# ZLS_Signal_Conditioner.net
KiCad netlist of a schematic drawn in Altium Designer
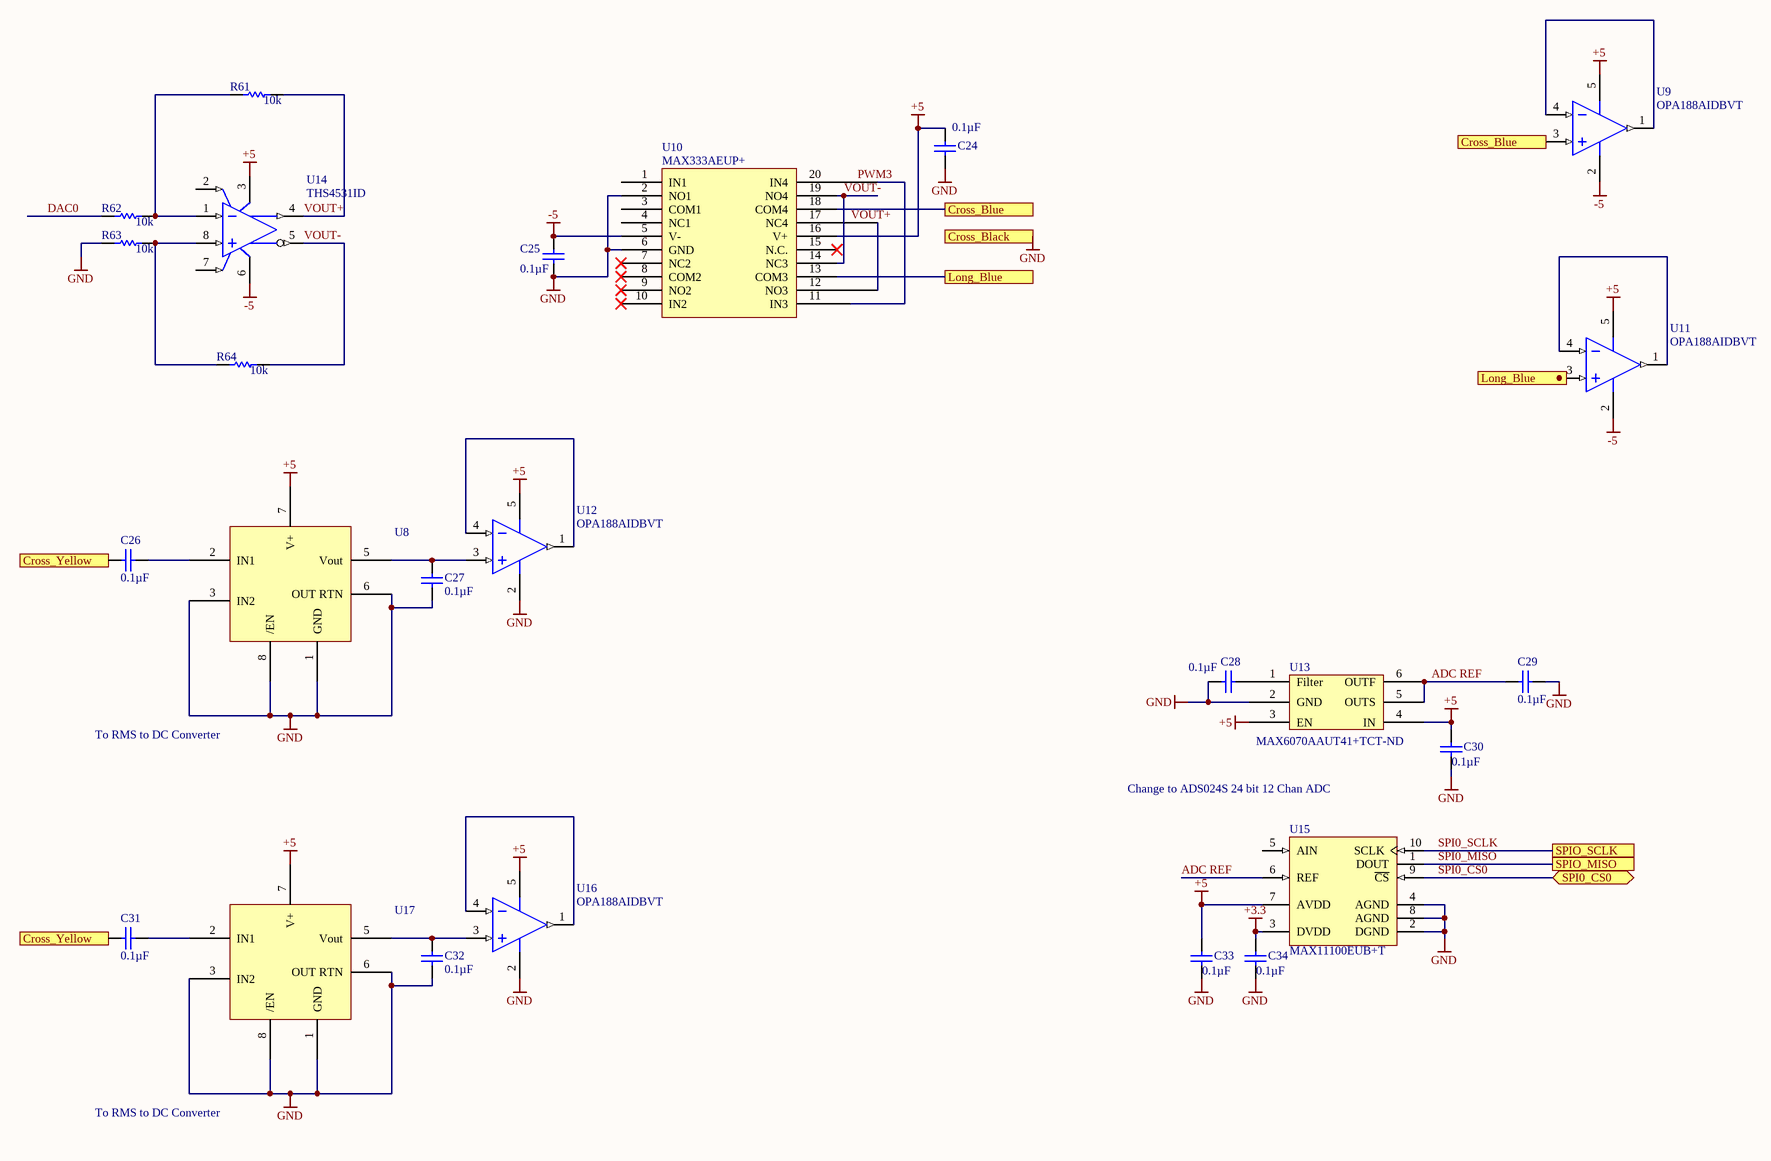
[diagram p0: ZLS_Signal_Conditioner.SchDoc]

(export (version "E")
  (design (tool "Eeschema 10.0.6"))
  (components
    (comp (ref "C24")
      (value "CAP CER 0.1UF 25V X7R 0805")
      (footprint "CAPC0805(2012)145_N")
      (fields
        (field (name "MANUFACTURER") "Murata Electronics North America")
        (field (name "MANUFACTURER PART NUMBER") "GRM21BR71E104KA01L")
        (field (name "CAPACITANCE") "0.1µF")
        (field (name "TOLERANCE") "±10%")
      )
      (libsource (lib "Altium Content Vault") (part "CMP-1036-04795-1"))
    )
    (comp (ref "C25")
      (value "CAP CER 0.1UF 25V X7R 0805")
      (footprint "CAPC0805(2012)145_N")
      (fields
        (field (name "MANUFACTURER") "Murata Electronics North America")
        (field (name "MANUFACTURER PART NUMBER") "GRM21BR71E104KA01L")
        (field (name "CAPACITANCE") "0.1µF")
        (field (name "TOLERANCE") "±10%")
      )
      (libsource (lib "Altium Content Vault") (part "CMP-1036-04795-1"))
    )
    (comp (ref "C26")
      (value "CAP CER 0.1UF 25V X7R 0805")
      (footprint "CAPC0805(2012)145_N")
      (fields
        (field (name "MANUFACTURER") "Murata Electronics North America")
        (field (name "MANUFACTURER PART NUMBER") "GRM21BR71E104KA01L")
        (field (name "CAPACITANCE") "0.1µF")
        (field (name "TOLERANCE") "±10%")
      )
      (libsource (lib "Altium Content Vault") (part "CMP-1036-04795-1"))
    )
    (comp (ref "C27")
      (value "CAP CER 0.1UF 25V X7R 0805")
      (footprint "CAPC0805(2012)145_N")
      (fields
        (field (name "MANUFACTURER") "Murata Electronics North America")
        (field (name "MANUFACTURER PART NUMBER") "GRM21BR71E104KA01L")
        (field (name "CAPACITANCE") "0.1µF")
        (field (name "TOLERANCE") "±10%")
      )
      (libsource (lib "Altium Content Vault") (part "CMP-1036-04795-1"))
    )
    (comp (ref "C28")
      (value "CAP CER 0.1UF 25V X7R 0805")
      (footprint "CAPC0805(2012)145_N")
      (fields
        (field (name "MANUFACTURER") "Murata Electronics North America")
        (field (name "MANUFACTURER PART NUMBER") "GRM21BR71E104KA01L")
        (field (name "CAPACITANCE") "0.1µF")
        (field (name "TOLERANCE") "±10%")
      )
      (libsource (lib "Altium Content Vault") (part "CMP-1036-04795-1"))
    )
    (comp (ref "C29")
      (value "CAP CER 0.1UF 25V X7R 0805")
      (footprint "CAPC0805(2012)145_N")
      (fields
        (field (name "MANUFACTURER") "Murata Electronics North America")
        (field (name "MANUFACTURER PART NUMBER") "GRM21BR71E104KA01L")
        (field (name "CAPACITANCE") "0.1µF")
        (field (name "TOLERANCE") "±10%")
      )
      (libsource (lib "Altium Content Vault") (part "CMP-1036-04795-1"))
    )
    (comp (ref "C30")
      (value "CAP CER 0.1UF 25V X7R 0805")
      (footprint "CAPC0805(2012)145_N")
      (fields
        (field (name "MANUFACTURER") "Murata Electronics North America")
        (field (name "MANUFACTURER PART NUMBER") "GRM21BR71E104KA01L")
        (field (name "CAPACITANCE") "0.1µF")
        (field (name "TOLERANCE") "±10%")
      )
      (libsource (lib "Altium Content Vault") (part "CMP-1036-04795-1"))
    )
    (comp (ref "C31")
      (value "CAP CER 0.1UF 25V X7R 0805")
      (footprint "CAPC0805(2012)145_N")
      (fields
        (field (name "MANUFACTURER") "Murata Electronics North America")
        (field (name "MANUFACTURER PART NUMBER") "GRM21BR71E104KA01L")
        (field (name "CAPACITANCE") "0.1µF")
        (field (name "TOLERANCE") "±10%")
      )
      (libsource (lib "Altium Content Vault") (part "CMP-1036-04795-1"))
    )
    (comp (ref "C32")
      (value "CAP CER 0.1UF 25V X7R 0805")
      (footprint "CAPC0805(2012)145_N")
      (fields
        (field (name "MANUFACTURER") "Murata Electronics North America")
        (field (name "MANUFACTURER PART NUMBER") "GRM21BR71E104KA01L")
        (field (name "CAPACITANCE") "0.1µF")
        (field (name "TOLERANCE") "±10%")
      )
      (libsource (lib "Altium Content Vault") (part "CMP-1036-04795-1"))
    )
    (comp (ref "C33")
      (value "CAP CER 0.1UF 25V X7R 0805")
      (footprint "CAPC0805(2012)145_N")
      (fields
        (field (name "MANUFACTURER") "Murata Electronics North America")
        (field (name "MANUFACTURER PART NUMBER") "GRM21BR71E104KA01L")
        (field (name "CAPACITANCE") "0.1µF")
        (field (name "TOLERANCE") "±10%")
      )
      (libsource (lib "Altium Content Vault") (part "CMP-1036-04795-1"))
    )
    (comp (ref "C34")
      (value "CAP CER 0.1UF 25V X7R 0805")
      (footprint "CAPC0805(2012)145_N")
      (fields
        (field (name "MANUFACTURER") "Murata Electronics North America")
        (field (name "MANUFACTURER PART NUMBER") "GRM21BR71E104KA01L")
        (field (name "CAPACITANCE") "0.1µF")
        (field (name "TOLERANCE") "±10%")
      )
      (libsource (lib "Altium Content Vault") (part "CMP-1036-04795-1"))
    )
    (comp (ref "R61")
      (value "10k")
      (footprint "RESC0805(2012)_L")
      (description "RES SMD 10K OHM 1% 1/8W 0805")
      (fields
        (field (name "MANUFACTURER") "Vishay Dale")
        (field (name "MANUFACTURER PART NUMBER") "CRCW080510K0FKEA")
      )
      (libsource (lib "Altium Content Vault") (part "CMP-1013-00393-1"))
    )
    (comp (ref "R62")
      (value "10k")
      (footprint "RESC0805(2012)_L")
      (description "RES SMD 10K OHM 1% 1/8W 0805")
      (fields
        (field (name "MANUFACTURER") "Vishay Dale")
        (field (name "MANUFACTURER PART NUMBER") "CRCW080510K0FKEA")
      )
      (libsource (lib "Altium Content Vault") (part "CMP-1013-00393-1"))
    )
    (comp (ref "R63")
      (value "10k")
      (footprint "RESC0805(2012)_L")
      (description "RES SMD 10K OHM 1% 1/8W 0805")
      (fields
        (field (name "MANUFACTURER") "Vishay Dale")
        (field (name "MANUFACTURER PART NUMBER") "CRCW080510K0FKEA")
      )
      (libsource (lib "Altium Content Vault") (part "CMP-1013-00393-1"))
    )
    (comp (ref "R64")
      (value "10k")
      (footprint "RESC0805(2012)_L")
      (description "RES SMD 10K OHM 1% 1/8W 0805")
      (fields
        (field (name "MANUFACTURER") "Vishay Dale")
        (field (name "MANUFACTURER PART NUMBER") "CRCW080510K0FKEA")
      )
      (libsource (lib "Altium Content Vault") (part "CMP-1013-00393-1"))
    )
    (comp (ref "U8")
      (value "LTC1967")
      (footprint "LTC1967")
      (description "IC CONVERTER RMS-DC PREC 9MSOP")
      (libsource (lib "ZLS_Schematic_lib") (part "LTC1967"))
    )
    (comp (ref "U9")
      (value "OPA188AIDBVT")
      (footprint "DBV0005A_L")
      (fields (field (name "MANUFACTURER") "Texas Instruments"))
      (libsource (lib "Altium Content Vault") (part "TI-OPA188-DBV5"))
    )
    (comp (ref "U10")
      (value "MAX333AEUP+")
      (footprint "TSOP65P640X90-20N")
      (description "IC SWITCH QUAD SPDT 20TSSOP")
      (fields (field (name "MANUFACTURER") "Maxim Integrated") (field (name "BASE PART NUMBER") "MAX333"))
      (libsource (lib "ZLS_Schematic_lib") (part "MAX333CWP+"))
    )
    (comp (ref "U11")
      (value "OPA188AIDBVT")
      (footprint "DBV0005A_L")
      (fields (field (name "MANUFACTURER") "Texas Instruments"))
      (libsource (lib "Altium Content Vault") (part "TI-OPA188-DBV5"))
    )
    (comp (ref "U12")
      (value "OPA188AIDBVT")
      (footprint "DBV0005A_L")
      (fields (field (name "MANUFACTURER") "Texas Instruments"))
      (libsource (lib "Altium Content Vault") (part "TI-OPA188-DBV5"))
    )
    (comp (ref "U13")
      (value "MAX6070AAUT41+T")
      (footprint "SOT95P280X445-6N")
      (description "IC VREF SERIES 4.096V SOT23")
      (fields
        (field (name "SUPPLIER PART NUMBER 1") "MAX6070AAUT41+TCT-ND")
        (field (name "MANUFACTURER") "Maxim Integrated")
        (field (name "TOLERANCE") "±0.04%")
      )
      (libsource (lib "ZLS_Schematic_lib") (part "MAX6070AAUT41+T"))
    )
    (comp (ref "U14")
      (value "THS4531ID")
      (footprint "D0008A_N")
      (fields (field (name "MANUFACTURER") "Texas Instruments"))
      (libsource (lib "Altium Content Vault") (part "CMP-0811-00005-2"))
    )
    (comp (ref "U15")
      (value "MAX11100EUB+T")
      (footprint "U10+2_L")
      (description "16-Bit, +5V, 200ksps ADC with 10uA Shutdown, 10-Pin uMAX, -40°C to +85°C, Pb-Free, Tape and Reel")
      (libsource (lib "Altium Content Vault") (part "CON-ADC-MAX11100-IL10"))
    )
    (comp (ref "U16")
      (value "OPA188AIDBVT")
      (footprint "DBV0005A_L")
      (fields (field (name "MANUFACTURER") "Texas Instruments"))
      (libsource (lib "Altium Content Vault") (part "TI-OPA188-DBV5"))
    )
    (comp (ref "U17")
      (value "LTC1967")
      (footprint "LTC1967")
      (description "IC CONVERTER RMS-DC PREC 9MSOP")
      (libsource (lib "ZLS_Schematic_lib") (part "LTC1967"))
    )
  )
  (nets
    (net (code "1") (name "+3.3") (class "Default")
      (node (ref "C34") (pin "1") (pinfunction "1_1") (pintype "passive"))
      (node (ref "U15") (pin "3") (pinfunction "DVDD_3") (pintype "power_in"))
    )
    (net (code "2") (name "+5") (class "Default")
      (node (ref "C24") (pin "1") (pinfunction "1_1") (pintype "passive"))
      (node (ref "C30") (pin "1") (pinfunction "1_1") (pintype "passive"))
      (node (ref "C33") (pin "1") (pinfunction "1_1") (pintype "passive"))
      (node (ref "U10") (pin "16") (pinfunction "V+_16") (pintype "power_in"))
      (node (ref "U11") (pin "5") (pinfunction "V+_5") (pintype "power_in"))
      (node (ref "U12") (pin "5") (pinfunction "V+_5") (pintype "power_in"))
      (node (ref "U13") (pin "3") (pinfunction "EN_3") (pintype "passive"))
      (node (ref "U13") (pin "4") (pinfunction "IN_4") (pintype "passive"))
      (node (ref "U14") (pin "3") (pinfunction "VS+_3") (pintype "power_in"))
      (node (ref "U15") (pin "7") (pinfunction "AVDD_7") (pintype "power_in"))
      (node (ref "U16") (pin "5") (pinfunction "V+_5") (pintype "power_in"))
      (node (ref "U17") (pin "7") (pinfunction "V+_7") (pintype "passive"))
      (node (ref "U8") (pin "7") (pinfunction "V+_7") (pintype "passive"))
      (node (ref "U9") (pin "5") (pinfunction "V+_5") (pintype "power_in"))
    )
    (net (code "3") (name "-5") (class "Default")
      (node (ref "C25") (pin "1") (pinfunction "1_1") (pintype "passive"))
      (node (ref "U10") (pin "5") (pinfunction "V-_5") (pintype "power_in"))
      (node (ref "U11") (pin "2") (pinfunction "V-_2") (pintype "power_in"))
      (node (ref "U14") (pin "6") (pinfunction "VS-_6") (pintype "power_in"))
      (node (ref "U9") (pin "2") (pinfunction "V-_2") (pintype "power_in"))
    )
    (net (code "4") (name "/ADC REF") (class "Default")
      (node (ref "C29") (pin "1") (pinfunction "1_1") (pintype "passive"))
      (node (ref "U13") (pin "5") (pinfunction "OUTS_5") (pintype "passive"))
      (node (ref "U13") (pin "6") (pinfunction "OUTF_6") (pintype "passive"))
      (node (ref "U15") (pin "6") (pinfunction "REF_6") (pintype "input"))
    )
    (net (code "5") (name "/Cross_Blue") (class "Default")
      (node (ref "U10") (pin "18") (pinfunction "COM4_18") (pintype "passive"))
      (node (ref "U9") (pin "3") (pinfunction "IN+_3") (pintype "input"))
    )
    (net (code "6") (name "/Cross_Yellow") (class "Default")
      (node (ref "C26") (pin "1") (pinfunction "1_1") (pintype "passive"))
      (node (ref "C31") (pin "1") (pinfunction "1_1") (pintype "passive"))
    )
    (net (code "7") (name "/DAC0") (class "Default")
      (node (ref "R62") (pin "1") (pinfunction "1_1") (pintype "passive"))
    )
    (net (code "8") (name "/Long_Blue") (class "Default")
      (node (ref "U10") (pin "13") (pinfunction "COM3_13") (pintype "passive"))
    )
    (net (code "9") (name "/PWM3") (class "Default")
      (node (ref "U10") (pin "11") (pinfunction "IN3_11") (pintype "passive"))
      (node (ref "U10") (pin "20") (pinfunction "IN4_20") (pintype "passive"))
    )
    (net (code "10") (name "/SPI0_CS0") (class "Default")
      (node (ref "U15") (pin "9") (pinfunction "~{CS}_9") (pintype "input"))
    )
    (net (code "11") (name "/SPI0_MISO") (class "Default")
      (node (ref "U15") (pin "1") (pinfunction "DOUT_1") (pintype "tri_state"))
    )
    (net (code "12") (name "/SPI0_SCLK") (class "Default")
      (node (ref "U15") (pin "10") (pinfunction "SCLK_10") (pintype "input"))
    )
    (net (code "13") (name "/VOUT+") (class "Default")
      (node (ref "R61") (pin "2") (pinfunction "2_2") (pintype "passive"))
      (node (ref "U10") (pin "12") (pinfunction "NO3_12") (pintype "passive"))
      (node (ref "U10") (pin "17") (pinfunction "NC4_17") (pintype "passive"))
      (node (ref "U14") (pin "4") (pinfunction "VOUT+_4") (pintype "output"))
    )
    (net (code "14") (name "/VOUT-") (class "Default")
      (node (ref "R64") (pin "2") (pinfunction "2_2") (pintype "passive"))
      (node (ref "U10") (pin "14") (pinfunction "NC3_14") (pintype "passive"))
      (node (ref "U10") (pin "19") (pinfunction "NO4_19") (pintype "passive"))
      (node (ref "U14") (pin "5") (pinfunction "VOUT-_5") (pintype "output"))
    )
    (net (code "15") (name "GND") (class "Default")
      (node (ref "C24") (pin "2") (pinfunction "2_2") (pintype "passive"))
      (node (ref "C25") (pin "2") (pinfunction "2_2") (pintype "passive"))
      (node (ref "C27") (pin "1") (pinfunction "1_1") (pintype "passive"))
      (node (ref "C28") (pin "1") (pinfunction "1_1") (pintype "passive"))
      (node (ref "C29") (pin "2") (pinfunction "2_2") (pintype "passive"))
      (node (ref "C30") (pin "2") (pinfunction "2_2") (pintype "passive"))
      (node (ref "C32") (pin "1") (pinfunction "1_1") (pintype "passive"))
      (node (ref "C33") (pin "2") (pinfunction "2_2") (pintype "passive"))
      (node (ref "C34") (pin "2") (pinfunction "2_2") (pintype "passive"))
      (node (ref "R63") (pin "1") (pinfunction "1_1") (pintype "passive"))
      (node (ref "U10") (pin "2") (pinfunction "NO1_2") (pintype "passive"))
      (node (ref "U10") (pin "6") (pinfunction "GND_6") (pintype "passive"))
      (node (ref "U12") (pin "2") (pinfunction "V-_2") (pintype "power_in"))
      (node (ref "U13") (pin "2") (pinfunction "GND_2") (pintype "passive"))
      (node (ref "U15") (pin "2") (pinfunction "DGND_2") (pintype "power_in"))
      (node (ref "U15") (pin "4") (pinfunction "AGND_4") (pintype "power_in"))
      (node (ref "U15") (pin "8") (pinfunction "AGND_8") (pintype "power_in"))
      (node (ref "U16") (pin "2") (pinfunction "V-_2") (pintype "power_in"))
      (node (ref "U17") (pin "1") (pinfunction "GND_1") (pintype "passive"))
      (node (ref "U17") (pin "3") (pinfunction "IN2_3") (pintype "passive"))
      (node (ref "U17") (pin "6") (pinfunction "OUT_RTN_6") (pintype "passive"))
      (node (ref "U17") (pin "8") (pinfunction "/EN_8") (pintype "passive"))
      (node (ref "U8") (pin "1") (pinfunction "GND_1") (pintype "passive"))
      (node (ref "U8") (pin "3") (pinfunction "IN2_3") (pintype "passive"))
      (node (ref "U8") (pin "6") (pinfunction "OUT_RTN_6") (pintype "passive"))
      (node (ref "U8") (pin "8") (pinfunction "/EN_8") (pintype "passive"))
    )
    (net (code "16") (name "Net-(U8-IN1)") (class "Default")
      (node (ref "C26") (pin "2") (pinfunction "2_2") (pintype "passive"))
      (node (ref "U8") (pin "2") (pinfunction "IN1_2") (pintype "passive"))
    )
    (net (code "17") (name "Net-(U9-IN-)") (class "Default")
      (node (ref "U9") (pin "1") (pinfunction "OUT_1") (pintype "output"))
      (node (ref "U9") (pin "4") (pinfunction "IN-_4") (pintype "input"))
    )
    (net (code "18") (name "Net-(U11-IN-)") (class "Default")
      (node (ref "U11") (pin "1") (pinfunction "OUT_1") (pintype "output"))
      (node (ref "U11") (pin "4") (pinfunction "IN-_4") (pintype "input"))
    )
    (net (code "19") (name "Net-(U12-IN+)") (class "Default")
      (node (ref "C27") (pin "2") (pinfunction "2_2") (pintype "passive"))
      (node (ref "U12") (pin "3") (pinfunction "IN+_3") (pintype "input"))
      (node (ref "U8") (pin "5") (pinfunction "Vout_5") (pintype "passive"))
    )
    (net (code "20") (name "Net-(U12-IN-)") (class "Default")
      (node (ref "U12") (pin "1") (pinfunction "OUT_1") (pintype "output"))
      (node (ref "U12") (pin "4") (pinfunction "IN-_4") (pintype "input"))
    )
    (net (code "21") (name "Net-(U13-Filter)") (class "Default")
      (node (ref "C28") (pin "2") (pinfunction "2_2") (pintype "passive"))
      (node (ref "U13") (pin "1") (pinfunction "Filter_1") (pintype "passive"))
    )
    (net (code "22") (name "Net-(U14-VIN+)") (class "Default")
      (node (ref "R63") (pin "2") (pinfunction "2_2") (pintype "passive"))
      (node (ref "R64") (pin "1") (pinfunction "1_1") (pintype "passive"))
      (node (ref "U14") (pin "8") (pinfunction "VIN+_8") (pintype "input"))
    )
    (net (code "23") (name "Net-(U14-VIN-)") (class "Default")
      (node (ref "R61") (pin "1") (pinfunction "1_1") (pintype "passive"))
      (node (ref "R62") (pin "2") (pinfunction "2_2") (pintype "passive"))
      (node (ref "U14") (pin "1") (pinfunction "VIN-_1") (pintype "input"))
    )
    (net (code "24") (name "Net-(U16-IN+)") (class "Default")
      (node (ref "C32") (pin "2") (pinfunction "2_2") (pintype "passive"))
      (node (ref "U16") (pin "3") (pinfunction "IN+_3") (pintype "input"))
      (node (ref "U17") (pin "5") (pinfunction "Vout_5") (pintype "passive"))
    )
    (net (code "25") (name "Net-(U16-IN-)") (class "Default")
      (node (ref "U16") (pin "1") (pinfunction "OUT_1") (pintype "output"))
      (node (ref "U16") (pin "4") (pinfunction "IN-_4") (pintype "input"))
    )
    (net (code "26") (name "Net-(U17-IN1)") (class "Default")
      (node (ref "C31") (pin "2") (pinfunction "2_2") (pintype "passive"))
      (node (ref "U17") (pin "2") (pinfunction "IN1_2") (pintype "passive"))
    )
    (net (code "27") (name "unconnected-(U8-NC-Pad4)") (class "Default")
      (node (ref "U8") (pin "4") (pinfunction "NC_4") (pintype "passive"))
    )
    (net (code "28") (name "unconnected-(U10-COM1-Pad3)") (class "Default")
      (node (ref "U10") (pin "3") (pinfunction "COM1_3") (pintype "passive"))
    )
    (net (code "29") (name "unconnected-(U10-COM2-Pad8)") (class "Default")
      (node (ref "U10") (pin "8") (pinfunction "COM2_8") (pintype "passive+no_connect"))
    )
    (net (code "30") (name "unconnected-(U10-IN1-Pad1)") (class "Default")
      (node (ref "U10") (pin "1") (pinfunction "IN1_1") (pintype "passive"))
    )
    (net (code "31") (name "unconnected-(U10-IN2-Pad10)") (class "Default")
      (node (ref "U10") (pin "10") (pinfunction "IN2_10") (pintype "passive+no_connect"))
    )
    (net (code "32") (name "unconnected-(U10-N.C.-Pad15)") (class "Default")
      (node (ref "U10") (pin "15") (pinfunction "N.C._15") (pintype "passive+no_connect"))
    )
    (net (code "33") (name "unconnected-(U10-NC1-Pad4)") (class "Default")
      (node (ref "U10") (pin "4") (pinfunction "NC1_4") (pintype "passive"))
    )
    (net (code "34") (name "unconnected-(U10-NC2-Pad7)") (class "Default")
      (node (ref "U10") (pin "7") (pinfunction "NC2_7") (pintype "passive+no_connect"))
    )
    (net (code "35") (name "unconnected-(U10-NO2-Pad9)") (class "Default")
      (node (ref "U10") (pin "9") (pinfunction "NO2_9") (pintype "passive+no_connect"))
    )
    (net (code "36") (name "unconnected-(U11-IN+-Pad3)") (class "Default")
      (node (ref "U11") (pin "3") (pinfunction "IN+_3") (pintype "input"))
    )
    (net (code "37") (name "unconnected-(U14-VOCM-Pad2)") (class "Default")
      (node (ref "U14") (pin "2") (pinfunction "VOCM_2") (pintype "input"))
    )
    (net (code "38") (name "unconnected-(U14-~{PD}-Pad7)") (class "Default")
      (node (ref "U14") (pin "7") (pinfunction "~{PD}_7") (pintype "input"))
    )
    (net (code "39") (name "unconnected-(U15-AIN-Pad5)") (class "Default")
      (node (ref "U15") (pin "5") (pinfunction "AIN_5") (pintype "input"))
    )
    (net (code "40") (name "unconnected-(U17-NC-Pad4)") (class "Default")
      (node (ref "U17") (pin "4") (pinfunction "NC_4") (pintype "passive"))
    )
  )
)
